# flasher_without_opto.net
KiCad netlist of a schematic drawn in EAGLE
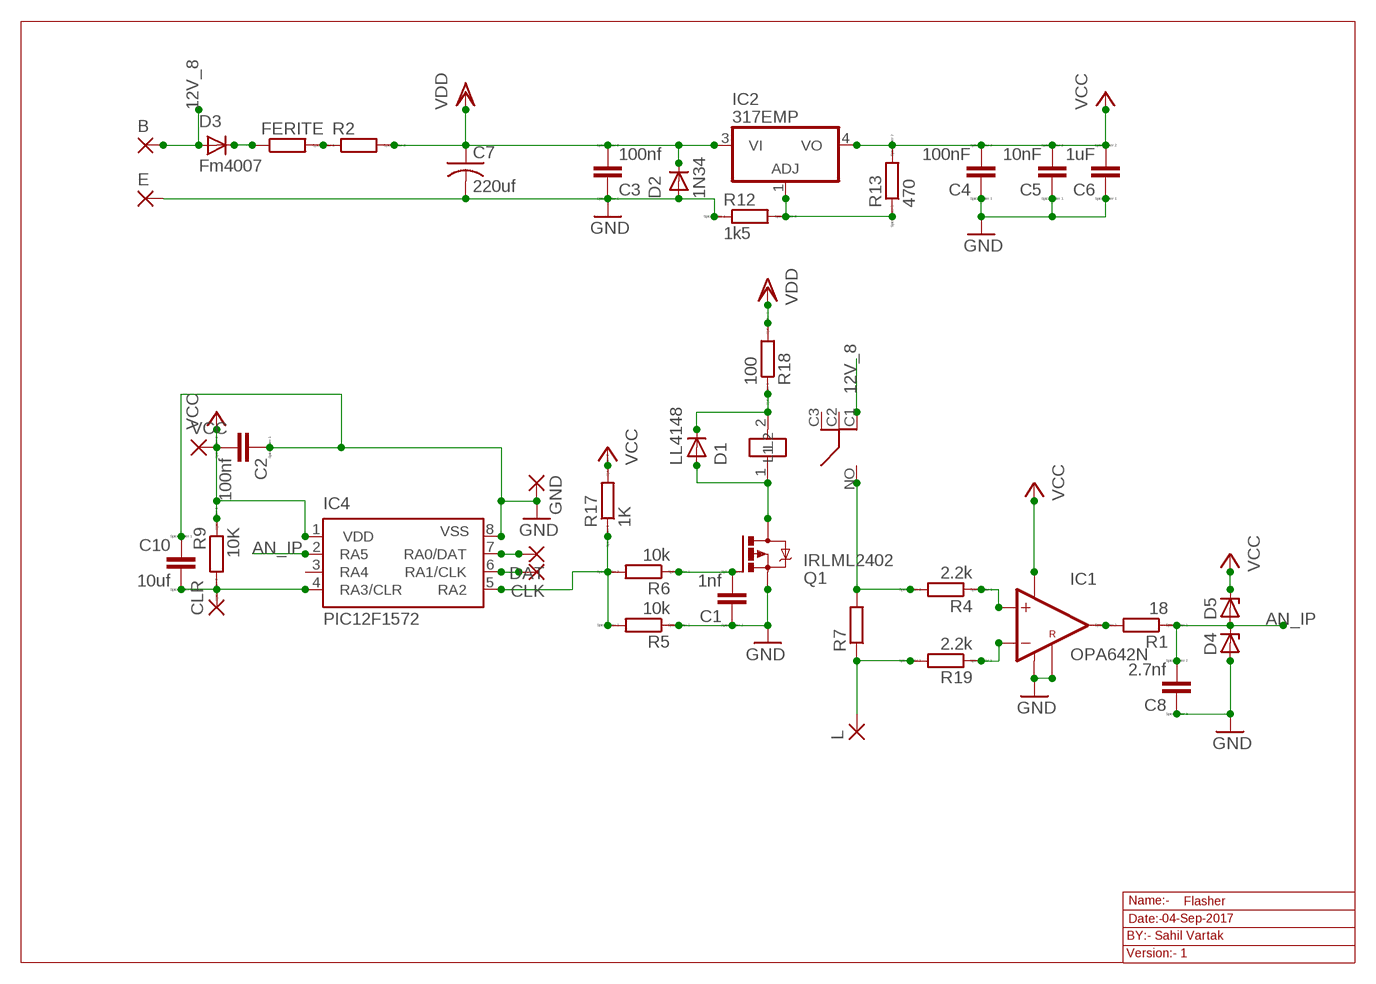
[diagram p0: schematic, sheet 1]

(export (version "E")
  (design (tool "Eeschema 10.0.6"))
  (components
    (comp (ref "B")
      (value "2,54/1,1")
      (footprint "eagle-import:2,54_1,1")
      (libsource (lib "eagle-import") (part "2,54/1,1"))
    )
    (comp (ref "C1")
      (value "1nf")
      (footprint "eagle-import:C0603")
      (libsource (lib "eagle-import") (part "CC0603"))
    )
    (comp (ref "C2")
      (value "100nf")
      (footprint "eagle-import:C0603")
      (libsource (lib "eagle-import") (part "CC0603"))
    )
    (comp (ref "C3")
      (value "100nf")
      (footprint "eagle-import:C0603")
      (libsource (lib "eagle-import") (part "CC0603"))
    )
    (comp (ref "C4")
      (value "100nF")
      (footprint "eagle-import:C0603")
      (libsource (lib "eagle-import") (part "CC0603"))
    )
    (comp (ref "C5")
      (value "10nF")
      (footprint "eagle-import:C0603")
      (libsource (lib "eagle-import") (part "CC0603"))
    )
    (comp (ref "C6")
      (value "1uF")
      (footprint "eagle-import:C0603")
      (libsource (lib "eagle-import") (part "CC0603"))
    )
    (comp (ref "C7")
      (value "220uf")
      (footprint "eagle-import:C025-025X050")
      (libsource (lib "eagle-import") (part "C-US025-025X050"))
    )
    (comp (ref "C8")
      (value "2.7nf")
      (footprint "eagle-import:C0603")
      (libsource (lib "eagle-import") (part "CC0603"))
    )
    (comp (ref "C10")
      (value "10uf")
      (footprint "eagle-import:C0603")
      (libsource (lib "eagle-import") (part "CC0603"))
    )
    (comp (ref "CLK")
      (value "1,6/0,8")
      (footprint "eagle-import:1,6_0,8")
      (libsource (lib "eagle-import") (part "1,6/0,8"))
    )
    (comp (ref "CLR")
      (value "1,6/0,8")
      (footprint "eagle-import:1,6_0,8")
      (libsource (lib "eagle-import") (part "1,6/0,8"))
    )
    (comp (ref "D1")
      (value "LL4148")
      (footprint "eagle-import:SMA-DO214AC")
      (libsource (lib "eagle-import") (part "GF1"))
    )
    (comp (ref "D2")
      (value "1N34")
      (footprint "eagle-import:SMA-DO214AC")
      (libsource (lib "eagle-import") (part "GF1"))
    )
    (comp (ref "D3")
      (value "Fm4007")
      (footprint "eagle-import:SMA-DO214AC")
      (libsource (lib "eagle-import") (part "GF1"))
    )
    (comp (ref "D4")
      (value "ZENER-DIODESOD80C")
      (footprint "eagle-import:SOD80C")
      (libsource (lib "eagle-import") (part "ZENER-DIODESOD80C"))
    )
    (comp (ref "D5")
      (value "ZENER-DIODESOD80C")
      (footprint "eagle-import:SOD80C")
      (libsource (lib "eagle-import") (part "ZENER-DIODESOD80C"))
    )
    (comp (ref "DAT")
      (value "1,6/0,8")
      (footprint "eagle-import:1,6_0,8")
      (libsource (lib "eagle-import") (part "1,6/0,8"))
    )
    (comp (ref "E")
      (value "2,54/1,1")
      (footprint "eagle-import:2,54_1,1")
      (libsource (lib "eagle-import") (part "2,54/1,1"))
    )
    (comp (ref "FERITE")
      (value "R-EU_R0603")
      (footprint "eagle-import:R0603")
      (libsource (lib "eagle-import") (part "R-EU_R0603"))
    )
    (comp (ref "GND")
      (value "1,6/0,8")
      (footprint "eagle-import:1,6_0,8")
      (libsource (lib "eagle-import") (part "1,6/0,8"))
    )
    (comp (ref "IC1")
      (value "OPA642N")
      (footprint "eagle-import:INA181")
      (libsource (lib "eagle-import") (part "OPA642N"))
    )
    (comp (ref "IC2")
      (value "317EMP")
      (footprint "eagle-import:SOT223")
      (libsource (lib "eagle-import") (part "317EMP"))
    )
    (comp (ref "IC4")
      (value "PIC12F1572")
      (footprint "eagle-import:SO-08")
      (fields (field (name "MF") "MICROCHIP") (field (name "MPN") "PIC12F675-E/SN"))
      (libsource (lib "eagle-import") (part "PIC12F6SN75"))
    )
    (comp (ref "K2")
      (value "RL703")
      (footprint "eagle-import:RL703")
      (libsource (lib "eagle-import") (part "RL703"))
    )
    (comp (ref "L")
      (value "2,54/1,1")
      (footprint "eagle-import:2,54_1,1")
      (libsource (lib "eagle-import") (part "2,54/1,1"))
    )
    (comp (ref "Q1")
      (value "IRLML2402")
      (footprint "eagle-import:MICRO3")
      (libsource (lib "eagle-import") (part "IRLML5203"))
    )
    (comp (ref "R1")
      (value "18")
      (footprint "eagle-import:R0603")
      (libsource (lib "eagle-import") (part "RR0603"))
    )
    (comp (ref "R2")
      (value "RR5025")
      (footprint "eagle-import:R5025")
      (libsource (lib "eagle-import") (part "RR5025"))
    )
    (comp (ref "R4")
      (value "2.2k")
      (footprint "eagle-import:R0603")
      (libsource (lib "eagle-import") (part "RR0603"))
    )
    (comp (ref "R5")
      (value "10k")
      (footprint "eagle-import:R0603")
      (libsource (lib "eagle-import") (part "RR0603"))
    )
    (comp (ref "R6")
      (value "10k")
      (footprint "eagle-import:R0603")
      (libsource (lib "eagle-import") (part "RR0603"))
    )
    (comp (ref "R7")
      (value "R-EU_0207/15")
      (footprint "eagle-import:0207_15")
      (libsource (lib "eagle-import") (part "R-EU_0207/15"))
    )
    (comp (ref "R9")
      (value "10K")
      (footprint "eagle-import:R0603")
      (libsource (lib "eagle-import") (part "RR0603"))
    )
    (comp (ref "R12")
      (value "1k5")
      (footprint "eagle-import:R0603")
      (libsource (lib "eagle-import") (part "RR0603"))
    )
    (comp (ref "R13")
      (value "470")
      (footprint "eagle-import:R0603")
      (libsource (lib "eagle-import") (part "RR0603"))
    )
    (comp (ref "R17")
      (value "1K")
      (footprint "eagle-import:R0603")
      (libsource (lib "eagle-import") (part "RR0603"))
    )
    (comp (ref "R18")
      (value "100")
      (footprint "eagle-import:R0603")
      (libsource (lib "eagle-import") (part "RR0603"))
    )
    (comp (ref "R19")
      (value "2.2k")
      (footprint "eagle-import:R0603")
      (libsource (lib "eagle-import") (part "RR0603"))
    )
    (comp (ref "VCC")
      (value "1,6/0,8")
      (footprint "eagle-import:1,6_0,8")
      (libsource (lib "eagle-import") (part "1,6/0,8"))
    )
  )
  (nets
    (net (code "1") (name "/12V_8") (class "Default")
      (node (ref "B") (pin "1") (pinfunction "P_1") (pintype "passive"))
      (node (ref "D3") (pin "A") (pinfunction "A_A") (pintype "passive"))
      (node (ref "K2") (pin "C1") (pinfunction "C1_C1") (pintype "bidirectional"))
    )
    (net (code "2") (name "/AN_IP") (class "Default")
      (node (ref "C8") (pin "2") (pinfunction "2_2") (pintype "passive"))
      (node (ref "D4") (pin "C") (pinfunction "C_C") (pintype "passive"))
      (node (ref "D5") (pin "A") (pinfunction "A_A") (pintype "passive"))
      (node (ref "IC4") (pin "2") (pinfunction "RA5_2") (pintype "bidirectional"))
      (node (ref "R1") (pin "1") (pinfunction "1_1") (pintype "passive"))
    )
    (net (code "3") (name "GND") (class "Default")
      (node (ref "C1") (pin "1") (pinfunction "1_1") (pintype "passive"))
      (node (ref "C10") (pin "1") (pinfunction "1_1") (pintype "passive"))
      (node (ref "C2") (pin "1") (pinfunction "1_1") (pintype "passive"))
      (node (ref "C3") (pin "1") (pinfunction "1_1") (pintype "passive"))
      (node (ref "C4") (pin "1") (pinfunction "1_1") (pintype "passive"))
      (node (ref "C5") (pin "1") (pinfunction "1_1") (pintype "passive"))
      (node (ref "C6") (pin "1") (pinfunction "1_1") (pintype "passive"))
      (node (ref "C7") (pin "2") (pinfunction "2_2") (pintype "passive"))
      (node (ref "C8") (pin "1") (pinfunction "1_1") (pintype "passive"))
      (node (ref "D2") (pin "A") (pinfunction "A_A") (pintype "passive"))
      (node (ref "D4") (pin "A") (pinfunction "A_A") (pintype "passive"))
      (node (ref "E") (pin "1") (pinfunction "P_1") (pintype "passive"))
      (node (ref "GND") (pin "1") (pinfunction "P_1") (pintype "passive"))
      (node (ref "IC1") (pin "P$2") (pinfunction "V-_P$2") (pintype "power_in"))
      (node (ref "IC1") (pin "P$5") (pinfunction "REF_P$5") (pintype "bidirectional"))
      (node (ref "IC4") (pin "8") (pinfunction "VSS_8") (pintype "power_in"))
      (node (ref "Q1") (pin "2") (pinfunction "S_2") (pintype "passive"))
      (node (ref "R12") (pin "1") (pinfunction "1_1") (pintype "passive"))
      (node (ref "R5") (pin "1") (pinfunction "1_1") (pintype "passive"))
    )
    (net (code "4") (name "Net-(CLK-P)") (class "Default")
      (node (ref "CLK") (pin "1") (pinfunction "P_1") (pintype "passive"))
      (node (ref "IC4") (pin "6") (pinfunction "RA1/CLK_6") (pintype "bidirectional"))
    )
    (net (code "5") (name "Net-(CLR-P)") (class "Default")
      (node (ref "C10") (pin "2") (pinfunction "2_2") (pintype "passive"))
      (node (ref "CLR") (pin "1") (pinfunction "P_1") (pintype "passive"))
      (node (ref "IC4") (pin "4") (pinfunction "RA3/CLR_4") (pintype "input"))
      (node (ref "R9") (pin "2") (pinfunction "2_2") (pintype "passive"))
    )
    (net (code "6") (name "Net-(D1-C)") (class "Default")
      (node (ref "D1") (pin "K") (pinfunction "C_K") (pintype "passive"))
      (node (ref "K2") (pin "2") (pinfunction "L1_2") (pintype "bidirectional"))
      (node (ref "R18") (pin "1") (pinfunction "1_1") (pintype "passive"))
    )
    (net (code "7") (name "Net-(D3-C)") (class "Default")
      (node (ref "D3") (pin "K") (pinfunction "C_K") (pintype "passive"))
      (node (ref "FERITE") (pin "1") (pinfunction "1_1") (pintype "passive"))
    )
    (net (code "8") (name "Net-(DAT-P)") (class "Default")
      (node (ref "DAT") (pin "1") (pinfunction "P_1") (pintype "passive"))
      (node (ref "IC4") (pin "7") (pinfunction "RA0/DAT_7") (pintype "bidirectional"))
    )
    (net (code "9") (name "Net-(FERITE-Pad2)") (class "Default")
      (node (ref "FERITE") (pin "2") (pinfunction "2_2") (pintype "passive"))
      (node (ref "R2") (pin "1") (pinfunction "1_1") (pintype "passive"))
    )
    (net (code "10") (name "Net-(IC1-+IN)") (class "Default")
      (node (ref "IC1") (pin "P$3") (pinfunction "+IN_P$3") (pintype "input"))
      (node (ref "R4") (pin "1") (pinfunction "1_1") (pintype "passive"))
    )
    (net (code "11") (name "Net-(IC1--IN)") (class "Default")
      (node (ref "IC1") (pin "P$4") (pinfunction "-IN_P$4") (pintype "input"))
      (node (ref "R19") (pin "1") (pinfunction "1_1") (pintype "passive"))
    )
    (net (code "12") (name "Net-(IC1-OUT)") (class "Default")
      (node (ref "IC1") (pin "P$1") (pinfunction "OUT_P$1") (pintype "output"))
      (node (ref "R1") (pin "2") (pinfunction "2_2") (pintype "passive"))
    )
    (net (code "13") (name "Net-(IC2-ADJ)") (class "Default")
      (node (ref "IC2") (pin "1") (pinfunction "ADJ_1") (pintype "input"))
      (node (ref "R12") (pin "2") (pinfunction "2_2") (pintype "passive"))
      (node (ref "R13") (pin "1") (pinfunction "1_1") (pintype "passive"))
    )
    (net (code "14") (name "Net-(IC4-RA2)") (class "Default")
      (node (ref "IC4") (pin "5") (pinfunction "RA2_5") (pintype "bidirectional"))
      (node (ref "R17") (pin "1") (pinfunction "1_1") (pintype "passive"))
      (node (ref "R5") (pin "2") (pinfunction "2_2") (pintype "passive"))
      (node (ref "R6") (pin "2") (pinfunction "2_2") (pintype "passive"))
    )
    (net (code "15") (name "Net-(K2-L2)") (class "Default")
      (node (ref "D1") (pin "A") (pinfunction "A_A") (pintype "passive"))
      (node (ref "K2") (pin "1") (pinfunction "L2_1") (pintype "bidirectional"))
      (node (ref "Q1") (pin "3") (pinfunction "D_3") (pintype "passive"))
    )
    (net (code "16") (name "Net-(K2-PadNO)") (class "Default")
      (node (ref "K2") (pin "NO") (pinfunction "NO_NO") (pintype "bidirectional"))
      (node (ref "R4") (pin "2") (pinfunction "2_2") (pintype "passive"))
      (node (ref "R7") (pin "2") (pinfunction "2_2") (pintype "passive"))
    )
    (net (code "17") (name "Net-(L-P)") (class "Default")
      (node (ref "L") (pin "1") (pinfunction "P_1") (pintype "passive"))
      (node (ref "R19") (pin "2") (pinfunction "2_2") (pintype "passive"))
      (node (ref "R7") (pin "1") (pinfunction "1_1") (pintype "passive"))
    )
    (net (code "18") (name "Net-(Q1-G)") (class "Default")
      (node (ref "C1") (pin "2") (pinfunction "2_2") (pintype "passive"))
      (node (ref "Q1") (pin "1") (pinfunction "G_1") (pintype "passive"))
      (node (ref "R6") (pin "1") (pinfunction "1_1") (pintype "passive"))
    )
    (net (code "19") (name "VCC") (class "Default")
      (node (ref "C2") (pin "2") (pinfunction "2_2") (pintype "passive"))
      (node (ref "C4") (pin "2") (pinfunction "2_2") (pintype "passive"))
      (node (ref "C5") (pin "2") (pinfunction "2_2") (pintype "passive"))
      (node (ref "C6") (pin "2") (pinfunction "2_2") (pintype "passive"))
      (node (ref "D5") (pin "C") (pinfunction "C_C") (pintype "passive"))
      (node (ref "IC1") (pin "P$6") (pinfunction "V+_P$6") (pintype "power_in"))
      (node (ref "IC2") (pin "4") (pinfunction "VO_4") (pintype "passive"))
      (node (ref "IC4") (pin "1") (pinfunction "VDD_1") (pintype "power_in"))
      (node (ref "R13") (pin "2") (pinfunction "2_2") (pintype "passive"))
      (node (ref "R17") (pin "2") (pinfunction "2_2") (pintype "passive"))
      (node (ref "R9") (pin "1") (pinfunction "1_1") (pintype "passive"))
      (node (ref "VCC") (pin "1") (pinfunction "P_1") (pintype "passive"))
    )
    (net (code "20") (name "VDD") (class "Default")
      (node (ref "C3") (pin "2") (pinfunction "2_2") (pintype "passive"))
      (node (ref "C7") (pin "1") (pinfunction "1_1") (pintype "passive"))
      (node (ref "D2") (pin "K") (pinfunction "C_K") (pintype "passive"))
      (node (ref "IC2") (pin "3") (pinfunction "VI_3") (pintype "input"))
      (node (ref "R18") (pin "2") (pinfunction "2_2") (pintype "passive"))
      (node (ref "R2") (pin "2") (pinfunction "2_2") (pintype "passive"))
    )
    (net (code "21") (name "unconnected-(IC4-RA4-Pad3)") (class "Default")
      (node (ref "IC4") (pin "3") (pinfunction "RA4_3") (pintype "bidirectional"))
    )
    (net (code "22") (name "unconnected-(K2-PadC2)") (class "Default")
      (node (ref "K2") (pin "C2") (pinfunction "C2_C2") (pintype "bidirectional"))
    )
    (net (code "23") (name "unconnected-(K2-PadC3)") (class "Default")
      (node (ref "K2") (pin "C3") (pinfunction "C3_C3") (pintype "bidirectional"))
    )
  )
)
